# EG701_BMS.net
KiCad netlist of a schematic drawn in Altium Designer
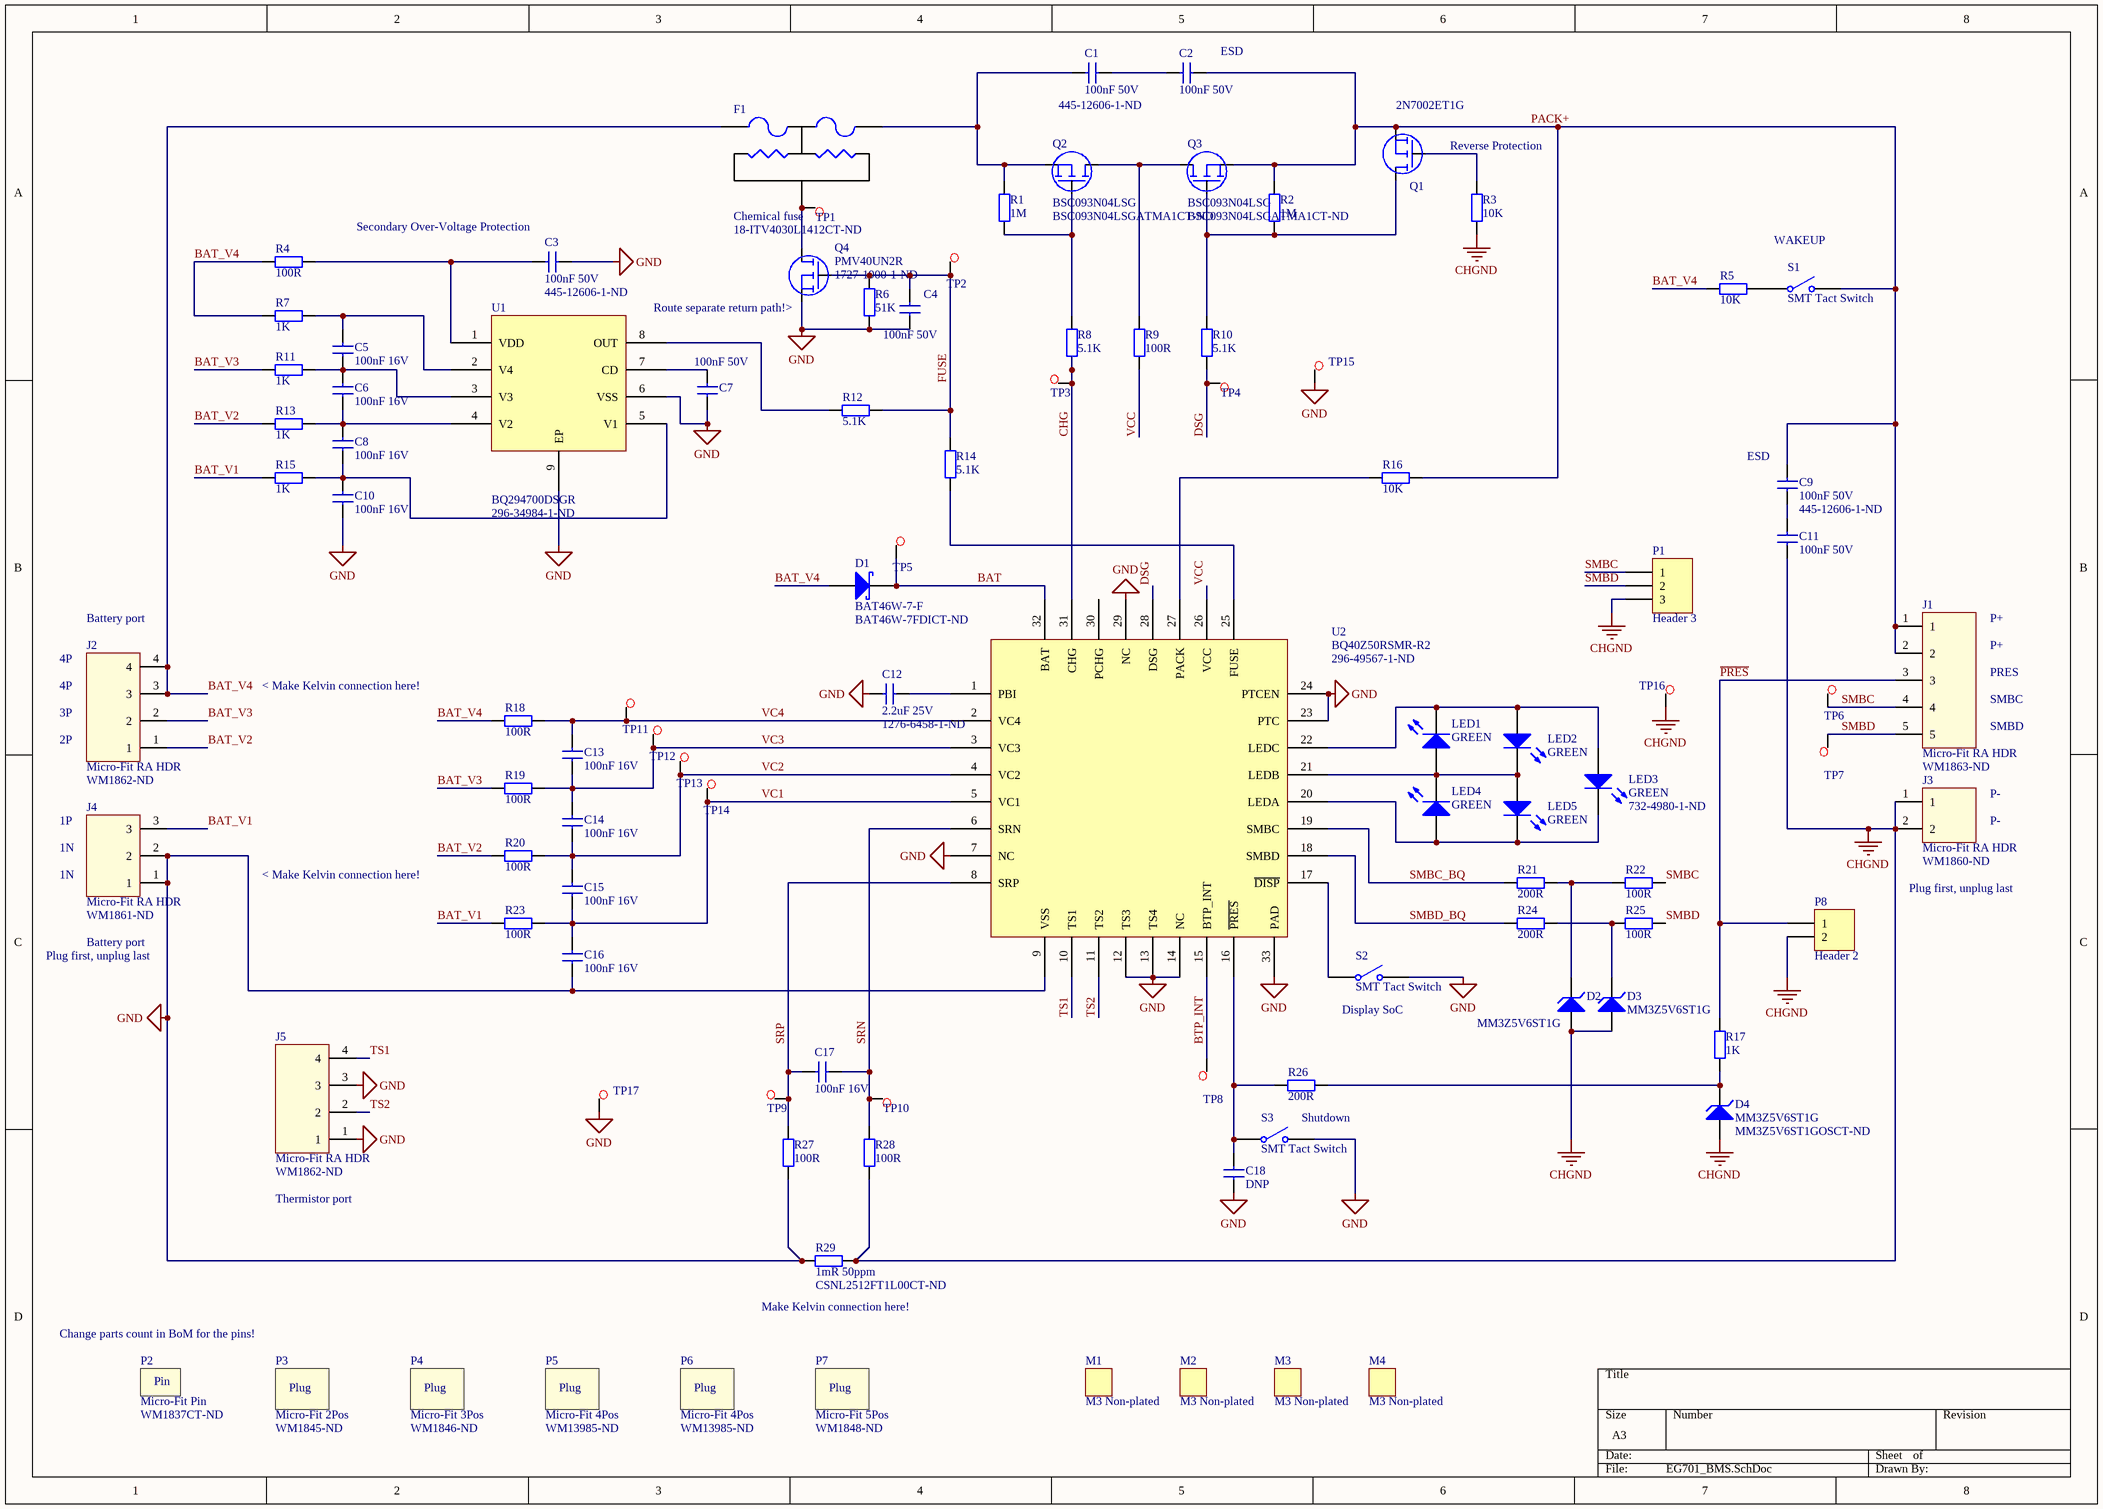
[diagram p0: EG701_BMS.SchDoc]

(export (version "E")
  (design (tool "Eeschema 10.0.6"))
  (components
    (comp (ref "C1")
      (value "100nF 50V")
      (footprint "C0603_GENERIC")
      (fields (field (name "TOLERANCE") "10%") (field (name "SUPPLIER PART NUMBER 1") "445-12606-1-ND"))
      (libsource (lib "FSAE47_Capacitors") (part "100nF_0603_10%_X8R_ 50V"))
    )
    (comp (ref "C2")
      (value "100nF 50V")
      (footprint "C0603_GENERIC")
      (fields (field (name "TOLERANCE") "10%"))
      (libsource (lib "FSAE47_Capacitors") (part "100nF_0603_10%_X8R_ 50V"))
    )
    (comp (ref "C3")
      (value "100nF 50V")
      (footprint "C0603_GENERIC")
      (fields (field (name "TOLERANCE") "10%") (field (name "SUPPLIER PART NUMBER 1") "445-12606-1-ND"))
      (libsource (lib "FSAE47_Capacitors") (part "100nF_0603_10%_X8R_ 50V"))
    )
    (comp (ref "C4")
      (value "100nF 50V")
      (footprint "C0603_GENERIC")
      (fields (field (name "TOLERANCE") "10%"))
      (libsource (lib "FSAE47_Capacitors") (part "100nF_0603_10%_X8R_ 50V"))
    )
    (comp (ref "C5")
      (value "100nF 16V")
      (footprint "C0603_GENERIC")
      (description "Cap Ceramic 0.1uF 16V Y5V -20% to 80% SMD 0603 85C Paper T/R")
      (fields (field (name "TOLERANCE") "80%"))
      (libsource (lib "FSAE47_Capacitors") (part "100nF_0603_-20%+80%_Y5V_16V"))
    )
    (comp (ref "C6")
      (value "100nF 16V")
      (footprint "C0603_GENERIC")
      (description "Cap Ceramic 0.1uF 16V Y5V -20% to 80% SMD 0603 85C Paper T/R")
      (fields (field (name "TOLERANCE") "80%"))
      (libsource (lib "FSAE47_Capacitors") (part "100nF_0603_-20%+80%_Y5V_16V"))
    )
    (comp (ref "C7")
      (value "100nF 50V")
      (footprint "C0603_GENERIC")
      (fields (field (name "TOLERANCE") "10%"))
      (libsource (lib "FSAE47_Capacitors") (part "100nF_0603_10%_X8R_ 50V"))
    )
    (comp (ref "C8")
      (value "100nF 16V")
      (footprint "C0603_GENERIC")
      (description "Cap Ceramic 0.1uF 16V Y5V -20% to 80% SMD 0603 85C Paper T/R")
      (fields (field (name "TOLERANCE") "80%"))
      (libsource (lib "FSAE47_Capacitors") (part "100nF_0603_-20%+80%_Y5V_16V"))
    )
    (comp (ref "C9")
      (value "100nF 50V")
      (footprint "C0603_GENERIC")
      (fields (field (name "TOLERANCE") "10%") (field (name "SUPPLIER PART NUMBER 1") "445-12606-1-ND"))
      (libsource (lib "FSAE47_Capacitors") (part "100nF_0603_10%_X8R_ 50V"))
    )
    (comp (ref "C10")
      (value "100nF 16V")
      (footprint "C0603_GENERIC")
      (description "Cap Ceramic 0.1uF 16V Y5V -20% to 80% SMD 0603 85C Paper T/R")
      (fields (field (name "TOLERANCE") "80%"))
      (libsource (lib "FSAE47_Capacitors") (part "100nF_0603_-20%+80%_Y5V_16V"))
    )
    (comp (ref "C11")
      (value "100nF 50V")
      (footprint "C0603_GENERIC")
      (fields (field (name "TOLERANCE") "10%"))
      (libsource (lib "FSAE47_Capacitors") (part "100nF_0603_10%_X8R_ 50V"))
    )
    (comp (ref "C12")
      (value "2.2uF 25V")
      (footprint "C0603_GENERIC")
      (description "Ceramic capacitor SMD 0805 2.2 µF 25 V 10 %")
      (fields (field (name "TOLERANCE") "10%") (field (name "SUPPLIER PART NUMBER 1") "1276-6458-1-ND"))
      (libsource (lib "EG701_BMS") (part "2U2_0603_10%_X5R_25V"))
    )
    (comp (ref "C13")
      (value "100nF 16V")
      (footprint "C0603_GENERIC")
      (description "Cap Ceramic 0.1uF 16V Y5V -20% to 80% SMD 0603 85C Paper T/R")
      (fields (field (name "TOLERANCE") "80%"))
      (libsource (lib "FSAE47_Capacitors") (part "100nF_0603_-20%+80%_Y5V_16V"))
    )
    (comp (ref "C14")
      (value "100nF 16V")
      (footprint "C0603_GENERIC")
      (description "Cap Ceramic 0.1uF 16V Y5V -20% to 80% SMD 0603 85C Paper T/R")
      (fields (field (name "TOLERANCE") "80%"))
      (libsource (lib "FSAE47_Capacitors") (part "100nF_0603_-20%+80%_Y5V_16V"))
    )
    (comp (ref "C15")
      (value "100nF 16V")
      (footprint "C0603_GENERIC")
      (description "Cap Ceramic 0.1uF 16V Y5V -20% to 80% SMD 0603 85C Paper T/R")
      (fields (field (name "TOLERANCE") "80%"))
      (libsource (lib "FSAE47_Capacitors") (part "100nF_0603_-20%+80%_Y5V_16V"))
    )
    (comp (ref "C16")
      (value "100nF 16V")
      (footprint "C0603_GENERIC")
      (description "Cap Ceramic 0.1uF 16V Y5V -20% to 80% SMD 0603 85C Paper T/R")
      (fields (field (name "TOLERANCE") "80%"))
      (libsource (lib "FSAE47_Capacitors") (part "100nF_0603_-20%+80%_Y5V_16V"))
    )
    (comp (ref "C17")
      (value "100nF 16V")
      (footprint "C0603_GENERIC")
      (description "Cap Ceramic 0.1uF 16V Y5V -20% to 80% SMD 0603 85C Paper T/R")
      (fields (field (name "TOLERANCE") "80%"))
      (libsource (lib "FSAE47_Capacitors") (part "100nF_0603_-20%+80%_Y5V_16V"))
    )
    (comp (ref "C18")
      (value "DNP")
      (footprint "C0603_GENERIC")
      (libsource (lib "FSAE47_Capacitors") (part "SMT_CAP_GENERIC"))
    )
    (comp (ref "D1")
      (value "BAT46W-7-F")
      (footprint "SOD-123_GENERIC")
      (description "Diode Schottky 100V 0.15A 2Pin SOD123")
      (fields (field (name "SUPPLIER PART NUMBER 1") "BAT46W-7FDICT-ND"))
      (libsource (lib "FSAE47_Diodes") (part "BAT46W-7-F"))
    )
    (comp (ref "D2")
      (value "MM3Z5V6ST1G")
      (footprint "SOD_323_GENERIC")
      (description "DIODE ZENER 5.6V 200MW SOD323")
      (fields (field (name "TOLERANCE") "2%"))
      (libsource (lib "EG701_BMS") (part "MM3Z5V6ST1G"))
    )
    (comp (ref "D3")
      (value "MM3Z5V6ST1G")
      (footprint "SOD_323_GENERIC")
      (description "DIODE ZENER 5.6V 200MW SOD323")
      (fields (field (name "TOLERANCE") "2%"))
      (libsource (lib "EG701_BMS") (part "MM3Z5V6ST1G"))
    )
    (comp (ref "D4")
      (value "MM3Z5V6ST1G")
      (footprint "SOD_323_GENERIC")
      (description "DIODE ZENER 5.6V 200MW SOD323")
      (fields (field (name "TOLERANCE") "2%") (field (name "SUPPLIER PART NUMBER 1") "MM3Z5V6ST1GOSCT-ND"))
      (libsource (lib "EG701_BMS") (part "MM3Z5V6ST1G"))
    )
    (comp (ref "F1")
      (value "Chemical fuse")
      (footprint "ITV4030Lxxxx")
      (description "36V 12A controllable fuse")
      (fields (field (name "SUPPLIER PART NUMBER 1") "18-ITV4030L1412CT-ND"))
      (libsource (lib "EG701_BMS") (part "ITV4030L1412"))
    )
    (comp (ref "J1")
      (value "Micro-Fit RA HDR")
      (footprint "436500500")
      (description "CONN HEADER R/A 5POS 3MM")
      (fields (field (name "SUPPLIER PART NUMBER 1") "WM1863-ND"))
      (libsource (lib "EG701_BMS") (part "43650-0500"))
    )
    (comp (ref "J2")
      (value "Micro-Fit RA HDR")
      (footprint "436500400")
      (fields (field (name "SUPPLIER PART NUMBER 1") "WM1862-ND"))
      (libsource (lib "EG701_BMS") (part "43650-0400"))
    )
    (comp (ref "J3")
      (value "Micro-Fit RA HDR")
      (footprint "436500200")
      (description "MOLEX   43650-0200   HEADER, R/A, SINGLE ROW, 2 WAY")
      (fields (field (name "SUPPLIER PART NUMBER 1") "WM1860-ND"))
      (libsource (lib "EG701_BMS") (part "43650-0200"))
    )
    (comp (ref "J4")
      (value "Micro-Fit RA HDR")
      (footprint "436500300")
      (fields (field (name "SUPPLIER PART NUMBER 1") "WM1861-ND"))
      (libsource (lib "EG701_BMS") (part "43650-0300"))
    )
    (comp (ref "J5")
      (value "Micro-Fit RA HDR")
      (footprint "436500400")
      (fields (field (name "SUPPLIER PART NUMBER 1") "WM1862-ND"))
      (libsource (lib "EG701_BMS") (part "43650-0400"))
    )
    (comp (ref "LED1")
      (value "GREEN")
      (footprint "LED_0603_GENERIC")
      (description "WURTH ELEKTRONIK - 150060VS75000 - LED, 0603, B GREEN,  40MCD, 570NM")
      (libsource (lib "FSAE47_Diodes") (part "150060VS75000"))
    )
    (comp (ref "LED2")
      (value "GREEN")
      (footprint "LED_0603_GENERIC")
      (description "WURTH ELEKTRONIK - 150060VS75000 - LED, 0603, B GREEN,  40MCD, 570NM")
      (libsource (lib "FSAE47_Diodes") (part "150060VS75000"))
    )
    (comp (ref "LED3")
      (value "GREEN")
      (footprint "LED_0603_GENERIC")
      (description "WURTH ELEKTRONIK - 150060VS75000 - LED, 0603, B GREEN,  40MCD, 570NM")
      (fields (field (name "SUPPLIER PART NUMBER 1") "732-4980-1-ND"))
      (libsource (lib "FSAE47_Diodes") (part "150060VS75000"))
    )
    (comp (ref "LED4")
      (value "GREEN")
      (footprint "LED_0603_GENERIC")
      (description "WURTH ELEKTRONIK - 150060VS75000 - LED, 0603, B GREEN,  40MCD, 570NM")
      (libsource (lib "FSAE47_Diodes") (part "150060VS75000"))
    )
    (comp (ref "LED5")
      (value "GREEN")
      (footprint "LED_0603_GENERIC")
      (description "WURTH ELEKTRONIK - 150060VS75000 - LED, 0603, B GREEN,  40MCD, 570NM")
      (libsource (lib "FSAE47_Diodes") (part "150060VS75000"))
    )
    (comp (ref "M1")
      (value "M3 Non-plated")
      (footprint "M3_NONPLATED_GENERIC")
      (description "Non-plated mounting hole, M3")
      (libsource (lib "FSAE47_Mechanical") (part "M3_NONPLATED"))
    )
    (comp (ref "M2")
      (value "M3 Non-plated")
      (footprint "M3_NONPLATED_GENERIC")
      (description "Non-plated mounting hole, M3")
      (libsource (lib "FSAE47_Mechanical") (part "M3_NONPLATED"))
    )
    (comp (ref "M3")
      (value "M3 Non-plated")
      (footprint "M3_NONPLATED_GENERIC")
      (description "Non-plated mounting hole, M3")
      (libsource (lib "FSAE47_Mechanical") (part "M3_NONPLATED"))
    )
    (comp (ref "M4")
      (value "M3 Non-plated")
      (footprint "M3_NONPLATED_GENERIC")
      (description "Non-plated mounting hole, M3")
      (libsource (lib "FSAE47_Mechanical") (part "M3_NONPLATED"))
    )
    (comp (ref "P1")
      (value "Header 3")
      (footprint "HDR3_3D")
      (description "Header, 3-Pin")
      (fields (field (name "PUBLISHER") "Altium Limited"))
      (libsource (lib "FSAE47_Connectors") (part "HDR3"))
    )
    (comp (ref "P2")
      (value "Micro-Fit Pin")
      (description "microfit 3.0 female crimp terminal 20-24 awg")
      (fields (field (name "SUPPLIER PART NUMBER 1") "WM1837CT-ND"))
      (libsource (lib "EG701_BMS") (part "43030-0001"))
    )
    (comp (ref "P3")
      (value "Micro-Fit 2Pos")
      (description "Female contact housing single row 3 mm Pole no. 1x2 Micro-Fit, 43645-0200, Molex")
      (fields (field (name "SUPPLIER PART NUMBER 1") "WM1845-ND"))
      (libsource (lib "EG701_BMS") (part "43645-0200"))
    )
    (comp (ref "P4")
      (value "Micro-Fit 3Pos")
      (description "MICRO-FIT 3.0 Series 3mm Pitch 3 Way 1 Row Female Straight PCB Housing 43645")
      (fields (field (name "SUPPLIER PART NUMBER 1") "WM1846-ND"))
      (libsource (lib "EG701_BMS") (part "43645-0300"))
    )
    (comp (ref "P5")
      (value "Micro-Fit 4Pos")
      (description "Conn Housing F 4 POS 3mm Crimp ST Cable Mount Micro-Fit 3.0™ Bag")
      (fields (field (name "SUPPLIER PART NUMBER 1") "WM13985-ND"))
      (libsource (lib "EG701_BMS") (part "43645-0408"))
    )
    (comp (ref "P6")
      (value "Micro-Fit 4Pos")
      (description "Conn Housing F 4 POS 3mm Crimp ST Cable Mount Micro-Fit 3.0™ Bag")
      (fields (field (name "SUPPLIER PART NUMBER 1") "WM13985-ND"))
      (libsource (lib "EG701_BMS") (part "43645-0408"))
    )
    (comp (ref "P7")
      (value "Micro-Fit 5Pos")
      (description "GLOVE, POLYAMIDE, L/FREE, PU, SIZE 6 - More Details")
      (fields (field (name "SUPPLIER PART NUMBER 1") "WM1848-ND"))
      (libsource (lib "EG701_BMS") (part "43645-0500"))
    )
    (comp (ref "P8")
      (value "Header 2")
      (footprint "HDR1X2")
      (description "Header, 2-Pin")
      (fields (field (name "PUBLISHER") "Altium Limited"))
      (libsource (lib "Miscellaneous Connectors") (part "Header 2"))
    )
    (comp (ref "Q1")
      (value "2N7002ET1G")
      (footprint "SOT-23_GENERIC")
      (description "Trans MOSFET N-CH 60V 0.26A 3-Pin SOT-23 T/R")
      (libsource (lib "FSAE47_Transistors") (part "2N7002ET1G"))
    )
    (comp (ref "Q2")
      (value "BSC093N04LSG")
      (footprint "TDSON-8")
      (description "Trans MOSFET N-CH 40V 13A 8-Pin TDSON T/R")
      (fields (field (name "SUPPLIER PART NUMBER 1") "BSC093N04LSGATMA1CT-ND"))
      (libsource (lib "EG701_BMS") (part "BSC093N04LSG"))
    )
    (comp (ref "Q3")
      (value "BSC093N04LSG")
      (footprint "TDSON-8")
      (description "Trans MOSFET N-CH 40V 13A 8-Pin TDSON T/R")
      (fields (field (name "SUPPLIER PART NUMBER 1") "BSC093N04LSGATMA1CT-ND"))
      (libsource (lib "EG701_BMS") (part "BSC093N04LSG"))
    )
    (comp (ref "Q4")
      (value "PMV40UN2R")
      (footprint "SOT-23_GENERIC")
      (description "PMV40UN2 Series 30 V 44 mOhm 3.7 A SMT N-Channel TrenchMOS FET - TO-236AB")
      (fields (field (name "SUPPLIER PART NUMBER 1") "1727-1900-1-ND"))
      (libsource (lib "EG701_BMS") (part "PMV40UN2R"))
    )
    (comp (ref "R1")
      (value "1M")
      (footprint "R0603_GENERIC")
      (description "Yageo RC Series Thick Film Surface Mount Resistor 0603 Case 1M 1% 0.1W 100ppm/C")
      (fields (field (name "TOLERANCE") "1%"))
      (libsource (lib "EG701_BMS") (part "1M_0603_1%_1/10W"))
    )
    (comp (ref "R2")
      (value "1M")
      (footprint "R0603_GENERIC")
      (description "Yageo RC Series Thick Film Surface Mount Resistor 0603 Case 1M 1% 0.1W 100ppm/C")
      (fields (field (name "TOLERANCE") "1%"))
      (libsource (lib "EG701_BMS") (part "1M_0603_1%_1/10W"))
    )
    (comp (ref "R3")
      (value "10K")
      (footprint "R0603_GENERIC")
      (description "RES SMD 10K OHM 1% 1/10W 0603")
      (fields (field (name "TOLERANCE") "1%"))
      (libsource (lib "") (part "10K_0603_1%_1/10W_1"))
    )
    (comp (ref "R4")
      (value "100R")
      (footprint "R0603_GENERIC")
      (description "Res Thick Film 0603 100 Ohm 5% 0.1W(1/10W) ±100ppm/C Molded SMD Paper T/R")
      (fields (field (name "TOLERANCE") "5%"))
      (libsource (lib "EG701_BMS") (part "100R_0603_5%_1/10W"))
    )
    (comp (ref "R5")
      (value "10K")
      (footprint "R0603_GENERIC")
      (description "RES SMD 10K OHM 1% 1/10W 0603")
      (fields (field (name "TOLERANCE") "1%"))
      (libsource (lib "FSAE47_Resistors") (part "10K_0603_1%_1/10W"))
    )
    (comp (ref "R6")
      (value "51K")
      (footprint "R0603_GENERIC")
      (description "RES SMD 51K OHM 1% 1/10W 0603")
      (fields (field (name "TOLERANCE") "1%"))
      (libsource (lib "EG701_BMS") (part "51K_0603_1%_1/10W"))
    )
    (comp (ref "R7")
      (value "1K")
      (footprint "R0603_GENERIC")
      (description "RES SMD 1K OHM 1% 1/10W 0603")
      (fields (field (name "TOLERANCE") "1%"))
      (libsource (lib "FSAE47_Resistors") (part "1K_0603_1%_1/10W"))
    )
    (comp (ref "R8")
      (value "5.1K")
      (footprint "R0603_GENERIC")
      (description "RES SMD 5.1K OHM 1% 1/10W 0603")
      (fields (field (name "TOLERANCE") "1%"))
      (libsource (lib "") (part "5K1_0603_1%_1/10W_1"))
    )
    (comp (ref "R9")
      (value "100R")
      (footprint "R0603_GENERIC")
      (description "Res Thick Film 0603 100 Ohm 5% 0.1W(1/10W) ±100ppm/C Molded SMD Paper T/R")
      (fields (field (name "TOLERANCE") "5%"))
      (libsource (lib "") (part "100R_0603_5%_1/10W_1"))
    )
    (comp (ref "R10")
      (value "5.1K")
      (footprint "R0603_GENERIC")
      (description "RES SMD 5.1K OHM 1% 1/10W 0603")
      (fields (field (name "TOLERANCE") "1%"))
      (libsource (lib "") (part "5K1_0603_1%_1/10W_1"))
    )
    (comp (ref "R11")
      (value "1K")
      (footprint "R0603_GENERIC")
      (description "RES SMD 1K OHM 1% 1/10W 0603")
      (fields (field (name "TOLERANCE") "1%"))
      (libsource (lib "FSAE47_Resistors") (part "1K_0603_1%_1/10W"))
    )
    (comp (ref "R12")
      (value "5.1K")
      (footprint "R0603_GENERIC")
      (description "RES SMD 5.1K OHM 1% 1/10W 0603")
      (fields (field (name "TOLERANCE") "1%"))
      (libsource (lib "EG701_BMS") (part "5K1_0603_1%_1/10W"))
    )
    (comp (ref "R13")
      (value "1K")
      (footprint "R0603_GENERIC")
      (description "RES SMD 1K OHM 1% 1/10W 0603")
      (fields (field (name "TOLERANCE") "1%"))
      (libsource (lib "FSAE47_Resistors") (part "1K_0603_1%_1/10W"))
    )
    (comp (ref "R14")
      (value "5.1K")
      (footprint "R0603_GENERIC")
      (description "RES SMD 5.1K OHM 1% 1/10W 0603")
      (fields (field (name "TOLERANCE") "1%"))
      (libsource (lib "") (part "5K1_0603_1%_1/10W_1"))
    )
    (comp (ref "R15")
      (value "1K")
      (footprint "R0603_GENERIC")
      (description "RES SMD 1K OHM 1% 1/10W 0603")
      (fields (field (name "TOLERANCE") "1%"))
      (libsource (lib "FSAE47_Resistors") (part "1K_0603_1%_1/10W"))
    )
    (comp (ref "R16")
      (value "10K")
      (footprint "R0603_GENERIC")
      (description "RES SMD 10K OHM 1% 1/10W 0603")
      (fields (field (name "TOLERANCE") "1%"))
      (libsource (lib "FSAE47_Resistors") (part "10K_0603_1%_1/10W"))
    )
    (comp (ref "R17")
      (value "1K")
      (footprint "R0603_GENERIC")
      (description "RES SMD 1K OHM 1% 1/10W 0603")
      (fields (field (name "TOLERANCE") "1%"))
      (libsource (lib "") (part "1K_0603_1%_1/10W_1"))
    )
    (comp (ref "R18")
      (value "100R")
      (footprint "R0603_GENERIC")
      (description "Res Thick Film 0603 100 Ohm 5% 0.1W(1/10W) ±100ppm/C Molded SMD Paper T/R")
      (fields (field (name "TOLERANCE") "5%"))
      (libsource (lib "EG701_BMS") (part "100R_0603_5%_1/10W"))
    )
    (comp (ref "R19")
      (value "100R")
      (footprint "R0603_GENERIC")
      (description "Res Thick Film 0603 100 Ohm 5% 0.1W(1/10W) ±100ppm/C Molded SMD Paper T/R")
      (fields (field (name "TOLERANCE") "5%"))
      (libsource (lib "EG701_BMS") (part "100R_0603_5%_1/10W"))
    )
    (comp (ref "R20")
      (value "100R")
      (footprint "R0603_GENERIC")
      (description "Res Thick Film 0603 100 Ohm 5% 0.1W(1/10W) ±100ppm/C Molded SMD Paper T/R")
      (fields (field (name "TOLERANCE") "5%"))
      (libsource (lib "EG701_BMS") (part "100R_0603_5%_1/10W"))
    )
    (comp (ref "R21")
      (value "200R")
      (footprint "R0603_GENERIC")
      (description "RES SMD 200 OHM 1% 1/10W 0603")
      (fields (field (name "TOLERANCE") "1%"))
      (libsource (lib "EG701_BMS") (part "200R_0603_1%_1/10W"))
    )
    (comp (ref "R22")
      (value "100R")
      (footprint "R0603_GENERIC")
      (description "Res Thick Film 0603 100 Ohm 5% 0.1W(1/10W) ±100ppm/C Molded SMD Paper T/R")
      (fields (field (name "TOLERANCE") "5%"))
      (libsource (lib "EG701_BMS") (part "100R_0603_5%_1/10W"))
    )
    (comp (ref "R23")
      (value "100R")
      (footprint "R0603_GENERIC")
      (description "Res Thick Film 0603 100 Ohm 5% 0.1W(1/10W) ±100ppm/C Molded SMD Paper T/R")
      (fields (field (name "TOLERANCE") "5%"))
      (libsource (lib "EG701_BMS") (part "100R_0603_5%_1/10W"))
    )
    (comp (ref "R24")
      (value "200R")
      (footprint "R0603_GENERIC")
      (description "RES SMD 200 OHM 1% 1/10W 0603")
      (fields (field (name "TOLERANCE") "1%"))
      (libsource (lib "EG701_BMS") (part "200R_0603_1%_1/10W"))
    )
    (comp (ref "R25")
      (value "100R")
      (footprint "R0603_GENERIC")
      (description "Res Thick Film 0603 100 Ohm 5% 0.1W(1/10W) ±100ppm/C Molded SMD Paper T/R")
      (fields (field (name "TOLERANCE") "5%"))
      (libsource (lib "EG701_BMS") (part "100R_0603_5%_1/10W"))
    )
    (comp (ref "R26")
      (value "200R")
      (footprint "R0603_GENERIC")
      (description "RES SMD 200 OHM 1% 1/10W 0603")
      (fields (field (name "TOLERANCE") "1%"))
      (libsource (lib "EG701_BMS") (part "200R_0603_1%_1/10W"))
    )
    (comp (ref "R27")
      (value "100R")
      (footprint "R0603_GENERIC")
      (description "Res Thick Film 0603 100 Ohm 5% 0.1W(1/10W) ±100ppm/C Molded SMD Paper T/R")
      (fields (field (name "TOLERANCE") "5%"))
      (libsource (lib "") (part "100R_0603_5%_1/10W_1"))
    )
    (comp (ref "R28")
      (value "100R")
      (footprint "R0603_GENERIC")
      (description "Res Thick Film 0603 100 Ohm 5% 0.1W(1/10W) ±100ppm/C Molded SMD Paper T/R")
      (fields (field (name "TOLERANCE") "5%"))
      (libsource (lib "") (part "100R_0603_5%_1/10W_1"))
    )
    (comp (ref "R29")
      (value "1mR 50ppm")
      (footprint "R2512_M_GENERIC")
      (description "RES 0.001 OHM 1% 2W 2512")
      (fields (field (name "TOLERANCE") "1%") (field (name "SUPPLIER PART NUMBER 1") "CSNL2512FT1L00CT-ND"))
      (libsource (lib "EG701_BMS") (part "0.001R_2512_1%_2W_50ppm"))
    )
    (comp (ref "S1")
      (value "SMT Tact Switch")
      (footprint "41-KRSM6-1")
      (description "SMT tact switch from Hi-Q")
      (libsource (lib "FSAE47_Switches") (part "41-KRSM6-1"))
    )
    (comp (ref "S2")
      (value "SMT Tact Switch")
      (footprint "41-KRSM6-1")
      (description "SMT tact switch from Hi-Q")
      (libsource (lib "FSAE47_Switches") (part "41-KRSM6-1"))
    )
    (comp (ref "S3")
      (value "SMT Tact Switch")
      (footprint "41-KRSM6-1")
      (description "SMT tact switch from Hi-Q")
      (libsource (lib "FSAE47_Switches") (part "41-KRSM6-1"))
    )
    (comp (ref "TP1")
      (value "Test Point TH")
      (footprint "TP_5021")
      (description "Thru Hole Mount Unisulated Test Point")
      (libsource (lib "EG701_BMS") (part "TP_5021"))
    )
    (comp (ref "TP2")
      (value "Test Point TH")
      (footprint "TP_5021")
      (description "Thru Hole Mount Unisulated Test Point")
      (libsource (lib "EG701_BMS") (part "TP_5021"))
    )
    (comp (ref "TP3")
      (value "Test Point TH")
      (footprint "TP_5021")
      (description "Thru Hole Mount Unisulated Test Point")
      (libsource (lib "EG701_BMS") (part "TP_5021"))
    )
    (comp (ref "TP4")
      (value "Test Point TH")
      (footprint "TP_5021")
      (description "Thru Hole Mount Unisulated Test Point")
      (libsource (lib "EG701_BMS") (part "TP_5021"))
    )
    (comp (ref "TP5")
      (value "Test Point TH")
      (footprint "TP_5021")
      (description "Thru Hole Mount Unisulated Test Point")
      (libsource (lib "EG701_BMS") (part "TP_5021"))
    )
    (comp (ref "TP6")
      (value "Test Point TH")
      (footprint "TP_5021")
      (description "Thru Hole Mount Unisulated Test Point")
      (libsource (lib "EG701_BMS") (part "TP_5021"))
    )
    (comp (ref "TP7")
      (value "Test Point TH")
      (footprint "TP_5021")
      (description "Thru Hole Mount Unisulated Test Point")
      (libsource (lib "EG701_BMS") (part "TP_5021"))
    )
    (comp (ref "TP8")
      (value "Test Point TH")
      (footprint "TP_5021")
      (description "Thru Hole Mount Unisulated Test Point")
      (libsource (lib "EG701_BMS") (part "TP_5021"))
    )
    (comp (ref "TP9")
      (value "Test Point TH")
      (footprint "TP_5021")
      (description "Thru Hole Mount Unisulated Test Point")
      (libsource (lib "EG701_BMS") (part "TP_5021"))
    )
    (comp (ref "TP10")
      (value "Test Point TH")
      (footprint "TP_5021")
      (description "Thru Hole Mount Unisulated Test Point")
      (libsource (lib "EG701_BMS") (part "TP_5021"))
    )
    (comp (ref "TP11")
      (value "Test Point TH")
      (footprint "TP_5021")
      (description "Thru Hole Mount Unisulated Test Point")
      (libsource (lib "EG701_BMS") (part "TP_5021"))
    )
    (comp (ref "TP12")
      (value "Test Point TH")
      (footprint "TP_5021")
      (description "Thru Hole Mount Unisulated Test Point")
      (libsource (lib "EG701_BMS") (part "TP_5021"))
    )
    (comp (ref "TP13")
      (value "Test Point TH")
      (footprint "TP_5021")
      (description "Thru Hole Mount Unisulated Test Point")
      (libsource (lib "EG701_BMS") (part "TP_5021"))
    )
    (comp (ref "TP14")
      (value "Test Point TH")
      (footprint "TP_5021")
      (description "Thru Hole Mount Unisulated Test Point")
      (libsource (lib "EG701_BMS") (part "TP_5021"))
    )
    (comp (ref "TP15")
      (value "Test Point TH")
      (footprint "TP_5021")
      (description "Thru Hole Mount Unisulated Test Point")
      (libsource (lib "EG701_BMS") (part "TP_5021"))
    )
    (comp (ref "TP16")
      (value "Test Point TH")
      (footprint "TP_5021")
      (description "Thru Hole Mount Unisulated Test Point")
      (libsource (lib "EG701_BMS") (part "TP_5021"))
    )
    (comp (ref "TP17")
      (value "Test Point TH")
      (footprint "TP_5021")
      (description "Thru Hole Mount Unisulated Test Point")
      (libsource (lib "EG701_BMS") (part "TP_5021"))
    )
    (comp (ref "U1")
      (value "BQ294700DSGR")
      (footprint "SON50P200X80_HS-9N")
      (description "IC BATT PROT 2-4CELL LIION 8WSON")
      (fields (field (name "SUPPLIER PART NUMBER 1") "296-34984-1-ND"))
      (libsource (lib "EG701_BMS") (part "BQ294700DSGR"))
    )
    (comp (ref "U2")
      (value "BQ40Z50RSMR-R2")
      (footprint "QFN40P400X400X100_HS-33N")
      (description "1-4 series Li-ion battery pack manager supporting Turbo Mode 2.0 32-VQFN -40 to 85")
      (fields (field (name "SUPPLIER PART NUMBER 1") "296-49567-1-ND"))
      (libsource (lib "EG701_BMS") (part "BQ40Z50RSMR-R2"))
    )
  )
  (nets
    (net (code "1") (name "/BAT") (class "Default")
      (node (ref "D1") (pin "2") (pinfunction "K_2") (pintype "passive"))
      (node (ref "TP5") (pin "1") (pinfunction "1_1") (pintype "passive"))
      (node (ref "U2") (pin "32") (pinfunction "BAT_32") (pintype "passive"))
    )
    (net (code "2") (name "/BAT_V1") (class "Default")
      (node (ref "J4") (pin "3") (pinfunction "3_3") (pintype "passive"))
      (node (ref "R15") (pin "1") (pinfunction "1_1") (pintype "passive"))
      (node (ref "R23") (pin "1") (pinfunction "1_1") (pintype "passive"))
    )
    (net (code "3") (name "/BAT_V2") (class "Default")
      (node (ref "J2") (pin "1") (pinfunction "1_1") (pintype "passive"))
      (node (ref "R13") (pin "1") (pinfunction "1_1") (pintype "passive"))
      (node (ref "R20") (pin "1") (pinfunction "1_1") (pintype "passive"))
    )
    (net (code "4") (name "/BAT_V3") (class "Default")
      (node (ref "J2") (pin "2") (pinfunction "2_2") (pintype "passive"))
      (node (ref "R11") (pin "1") (pinfunction "1_1") (pintype "passive"))
      (node (ref "R19") (pin "1") (pinfunction "1_1") (pintype "passive"))
    )
    (net (code "5") (name "/BAT_V4") (class "Default")
      (node (ref "D1") (pin "1") (pinfunction "A_1") (pintype "passive"))
      (node (ref "F1") (pin "3") (pinfunction "3_3") (pintype "passive"))
      (node (ref "J2") (pin "3") (pinfunction "3_3") (pintype "passive"))
      (node (ref "J2") (pin "4") (pinfunction "4_4") (pintype "passive"))
      (node (ref "R18") (pin "1") (pinfunction "1_1") (pintype "passive"))
      (node (ref "R4") (pin "1") (pinfunction "1_1") (pintype "passive"))
      (node (ref "R5") (pin "2") (pinfunction "2_2") (pintype "passive"))
      (node (ref "R7") (pin "1") (pinfunction "1_1") (pintype "passive"))
    )
    (net (code "6") (name "/BTP_INT") (class "Default")
      (node (ref "TP8") (pin "1") (pinfunction "1_1") (pintype "passive"))
      (node (ref "U2") (pin "15") (pinfunction "BTP_INT_15") (pintype "passive"))
    )
    (net (code "7") (name "/CHG") (class "Default")
      (node (ref "R8") (pin "1") (pinfunction "1_1") (pintype "passive"))
      (node (ref "TP3") (pin "1") (pinfunction "1_1") (pintype "passive"))
      (node (ref "U2") (pin "31") (pinfunction "CHG_31") (pintype "passive"))
    )
    (net (code "8") (name "/DSG") (class "Default")
      (node (ref "R10") (pin "1") (pinfunction "1_1") (pintype "passive"))
      (node (ref "TP4") (pin "1") (pinfunction "1_1") (pintype "passive"))
      (node (ref "U2") (pin "28") (pinfunction "DSG_28") (pintype "passive"))
    )
    (net (code "9") (name "/FUSE") (class "Default")
      (node (ref "C4") (pin "2") (pinfunction "2_2") (pintype "passive"))
      (node (ref "Q4") (pin "1") (pinfunction "G_1") (pintype "passive"))
      (node (ref "R12") (pin "2") (pinfunction "2_2") (pintype "passive"))
      (node (ref "R14") (pin "2") (pinfunction "2_2") (pintype "passive"))
      (node (ref "R6") (pin "2") (pinfunction "2_2") (pintype "passive"))
      (node (ref "TP2") (pin "1") (pinfunction "1_1") (pintype "passive"))
    )
    (net (code "10") (name "/PACK+") (class "Default")
      (node (ref "C2") (pin "2") (pinfunction "2_2") (pintype "passive"))
      (node (ref "C9") (pin "2") (pinfunction "2_2") (pintype "passive"))
      (node (ref "J1") (pin "1") (pinfunction "1_1") (pintype "passive"))
      (node (ref "J1") (pin "2") (pinfunction "2_2") (pintype "passive"))
      (node (ref "Q1") (pin "1") (pinfunction "S_1") (pintype "passive"))
      (node (ref "Q3") (pin "1") (pinfunction "S_1") (pintype "passive"))
      (node (ref "R16") (pin "1") (pinfunction "1_1") (pintype "passive"))
      (node (ref "R2") (pin "2") (pinfunction "2_2") (pintype "passive"))
      (node (ref "S1") (pin "2") (pinfunction "NO_2") (pintype "passive"))
    )
    (net (code "11") (name "/SMBC") (class "Default")
      (node (ref "J1") (pin "4") (pinfunction "4_4") (pintype "passive"))
      (node (ref "P1") (pin "1") (pinfunction "1_1") (pintype "passive"))
      (node (ref "R22") (pin "2") (pinfunction "2_2") (pintype "passive"))
      (node (ref "TP6") (pin "1") (pinfunction "1_1") (pintype "passive"))
    )
    (net (code "12") (name "/SMBC_BQ") (class "Default")
      (node (ref "R21") (pin "1") (pinfunction "1_1") (pintype "passive"))
      (node (ref "U2") (pin "19") (pinfunction "SMBC_19") (pintype "passive"))
    )
    (net (code "13") (name "/SMBD") (class "Default")
      (node (ref "J1") (pin "5") (pinfunction "5_5") (pintype "passive"))
      (node (ref "P1") (pin "2") (pinfunction "2_2") (pintype "passive"))
      (node (ref "R25") (pin "2") (pinfunction "2_2") (pintype "passive"))
      (node (ref "TP7") (pin "1") (pinfunction "1_1") (pintype "passive"))
    )
    (net (code "14") (name "/SMBD_BQ") (class "Default")
      (node (ref "R24") (pin "1") (pinfunction "1_1") (pintype "passive"))
      (node (ref "U2") (pin "18") (pinfunction "SMBD_18") (pintype "passive"))
    )
    (net (code "15") (name "/SRN") (class "Default")
      (node (ref "C17") (pin "1") (pinfunction "1_1") (pintype "passive"))
      (node (ref "R28") (pin "2") (pinfunction "2_2") (pintype "passive"))
      (node (ref "TP10") (pin "1") (pinfunction "1_1") (pintype "passive"))
      (node (ref "U2") (pin "6") (pinfunction "SRN_6") (pintype "passive"))
    )
    (net (code "16") (name "/SRP") (class "Default")
      (node (ref "C17") (pin "2") (pinfunction "2_2") (pintype "passive"))
      (node (ref "R27") (pin "2") (pinfunction "2_2") (pintype "passive"))
      (node (ref "TP9") (pin "1") (pinfunction "1_1") (pintype "passive"))
      (node (ref "U2") (pin "8") (pinfunction "SRP_8") (pintype "passive"))
    )
    (net (code "17") (name "/TS1") (class "Default")
      (node (ref "J5") (pin "4") (pinfunction "4_4") (pintype "passive"))
      (node (ref "U2") (pin "10") (pinfunction "TS1_10") (pintype "passive"))
    )
    (net (code "18") (name "/TS2") (class "Default")
      (node (ref "J5") (pin "2") (pinfunction "2_2") (pintype "passive"))
      (node (ref "U2") (pin "11") (pinfunction "TS2_11") (pintype "passive"))
    )
    (net (code "19") (name "/VC1") (class "Default")
      (node (ref "C15") (pin "1") (pinfunction "1_1") (pintype "passive"))
      (node (ref "C16") (pin "2") (pinfunction "2_2") (pintype "passive"))
      (node (ref "R23") (pin "2") (pinfunction "2_2") (pintype "passive"))
      (node (ref "TP14") (pin "1") (pinfunction "1_1") (pintype "passive"))
      (node (ref "U2") (pin "5") (pinfunction "VC1_5") (pintype "passive"))
    )
    (net (code "20") (name "/VC2") (class "Default")
      (node (ref "C14") (pin "1") (pinfunction "1_1") (pintype "passive"))
      (node (ref "C15") (pin "2") (pinfunction "2_2") (pintype "passive"))
      (node (ref "R20") (pin "2") (pinfunction "2_2") (pintype "passive"))
      (node (ref "TP13") (pin "1") (pinfunction "1_1") (pintype "passive"))
      (node (ref "U2") (pin "4") (pinfunction "VC2_4") (pintype "passive"))
    )
    (net (code "21") (name "/VC3") (class "Default")
      (node (ref "C13") (pin "1") (pinfunction "1_1") (pintype "passive"))
      (node (ref "C14") (pin "2") (pinfunction "2_2") (pintype "passive"))
      (node (ref "R19") (pin "2") (pinfunction "2_2") (pintype "passive"))
      (node (ref "TP12") (pin "1") (pinfunction "1_1") (pintype "passive"))
      (node (ref "U2") (pin "3") (pinfunction "VC3_3") (pintype "passive"))
    )
    (net (code "22") (name "/VC4") (class "Default")
      (node (ref "C13") (pin "2") (pinfunction "2_2") (pintype "passive"))
      (node (ref "R18") (pin "2") (pinfunction "2_2") (pintype "passive"))
      (node (ref "TP11") (pin "1") (pinfunction "1_1") (pintype "passive"))
      (node (ref "U2") (pin "2") (pinfunction "VC4_2") (pintype "passive"))
    )
    (net (code "23") (name "/VCC") (class "Default")
      (node (ref "R9") (pin "1") (pinfunction "1_1") (pintype "passive"))
      (node (ref "U2") (pin "26") (pinfunction "VCC_26") (pintype "passive"))
    )
    (net (code "24") (name "/~{PRES}") (class "Default")
      (node (ref "J1") (pin "3") (pinfunction "3_3") (pintype "passive"))
      (node (ref "P8") (pin "1") (pinfunction "1_1") (pintype "passive"))
      (node (ref "R17") (pin "2") (pinfunction "2_2") (pintype "passive"))
    )
    (net (code "25") (name "CHGND") (class "Default")
      (node (ref "C11") (pin "1") (pinfunction "1_1") (pintype "passive"))
      (node (ref "D2") (pin "1") (pinfunction "A_1") (pintype "passive"))
      (node (ref "D3") (pin "1") (pinfunction "A_1") (pintype "passive"))
      (node (ref "D4") (pin "1") (pinfunction "A_1") (pintype "passive"))
      (node (ref "J3") (pin "1") (pinfunction "1_1") (pintype "passive"))
      (node (ref "J3") (pin "2") (pinfunction "2_2") (pintype "passive"))
      (node (ref "P1") (pin "3") (pinfunction "3_3") (pintype "passive"))
      (node (ref "P8") (pin "2") (pinfunction "2_2") (pintype "passive"))
      (node (ref "R28") (pin "1") (pinfunction "1_1") (pintype "passive"))
      (node (ref "R29") (pin "2") (pinfunction "2_2") (pintype "passive"))
      (node (ref "R3") (pin "1") (pinfunction "1_1") (pintype "passive"))
      (node (ref "TP16") (pin "1") (pinfunction "1_1") (pintype "passive"))
    )
    (net (code "26") (name "GND") (class "Default")
      (node (ref "C10") (pin "1") (pinfunction "1_1") (pintype "passive"))
      (node (ref "C12") (pin "2") (pinfunction "2_2") (pintype "passive"))
      (node (ref "C16") (pin "1") (pinfunction "1_1") (pintype "passive"))
      (node (ref "C18") (pin "1") (pinfunction "1_1") (pintype "passive"))
      (node (ref "C3") (pin "1") (pinfunction "1_1") (pintype "passive"))
      (node (ref "C4") (pin "1") (pinfunction "1_1") (pintype "passive"))
      (node (ref "C7") (pin "1") (pinfunction "1_1") (pintype "passive"))
      (node (ref "J4") (pin "1") (pinfunction "1_1") (pintype "passive"))
      (node (ref "J4") (pin "2") (pinfunction "2_2") (pintype "passive"))
      (node (ref "J5") (pin "1") (pinfunction "1_1") (pintype "passive"))
      (node (ref "J5") (pin "3") (pinfunction "3_3") (pintype "passive"))
      (node (ref "Q4") (pin "2") (pinfunction "S_2") (pintype "passive"))
      (node (ref "R27") (pin "1") (pinfunction "1_1") (pintype "passive"))
      (node (ref "R29") (pin "1") (pinfunction "1_1") (pintype "passive"))
      (node (ref "R6") (pin "1") (pinfunction "1_1") (pintype "passive"))
      (node (ref "S2") (pin "2") (pinfunction "NO_2") (pintype "passive"))
      (node (ref "S3") (pin "2") (pinfunction "NO_2") (pintype "passive"))
      (node (ref "TP15") (pin "1") (pinfunction "1_1") (pintype "passive"))
      (node (ref "TP17") (pin "1") (pinfunction "1_1") (pintype "passive"))
      (node (ref "U1") (pin "6") (pinfunction "VSS_6") (pintype "passive"))
      (node (ref "U1") (pin "9") (pinfunction "EP_9") (pintype "passive"))
      (node (ref "U2") (pin "12") (pinfunction "TS3_12") (pintype "passive"))
      (node (ref "U2") (pin "13") (pinfunction "TS4_13") (pintype "passive"))
      (node (ref "U2") (pin "14") (pinfunction "NC_14") (pintype "passive"))
      (node (ref "U2") (pin "23") (pinfunction "PTC_23") (pintype "passive"))
      (node (ref "U2") (pin "24") (pinfunction "PTCEN_24") (pintype "passive"))
      (node (ref "U2") (pin "29") (pinfunction "NC_29") (pintype "passive"))
      (node (ref "U2") (pin "33") (pinfunction "PAD_33") (pintype "passive"))
      (node (ref "U2") (pin "7") (pinfunction "NC_7") (pintype "passive"))
      (node (ref "U2") (pin "9") (pinfunction "VSS_9") (pintype "passive"))
    )
    (net (code "27") (name "Net-(C1-Pad2)") (class "Default")
      (node (ref "C1") (pin "2") (pinfunction "2_2") (pintype "passive"))
      (node (ref "C2") (pin "1") (pinfunction "1_1") (pintype "passive"))
    )
    (net (code "28") (name "Net-(C11-Pad2)") (class "Default")
      (node (ref "C11") (pin "2") (pinfunction "2_2") (pintype "passive"))
      (node (ref "C9") (pin "1") (pinfunction "1_1") (pintype "passive"))
    )
    (net (code "29") (name "Net-(D2-K)") (class "Default")
      (node (ref "D2") (pin "2") (pinfunction "K_2") (pintype "passive"))
      (node (ref "R21") (pin "2") (pinfunction "2_2") (pintype "passive"))
      (node (ref "R22") (pin "1") (pinfunction "1_1") (pintype "passive"))
    )
    (net (code "30") (name "Net-(D3-K)") (class "Default")
      (node (ref "D3") (pin "2") (pinfunction "K_2") (pintype "passive"))
      (node (ref "R24") (pin "2") (pinfunction "2_2") (pintype "passive"))
      (node (ref "R25") (pin "1") (pinfunction "1_1") (pintype "passive"))
    )
    (net (code "31") (name "Net-(D4-K)") (class "Default")
      (node (ref "D4") (pin "2") (pinfunction "K_2") (pintype "passive"))
      (node (ref "R17") (pin "1") (pinfunction "1_1") (pintype "passive"))
      (node (ref "R26") (pin "2") (pinfunction "2_2") (pintype "passive"))
    )
    (net (code "32") (name "Net-(LED1-A)") (class "Default")
      (node (ref "LED1") (pin "2") (pinfunction "A_2") (pintype "passive"))
      (node (ref "LED2") (pin "1") (pinfunction "K_1") (pintype "passive"))
      (node (ref "LED4") (pin "1") (pinfunction "K_1") (pintype "passive"))
      (node (ref "LED5") (pin "2") (pinfunction "A_2") (pintype "passive"))
      (node (ref "U2") (pin "21") (pinfunction "LEDB_21") (pintype "passive"))
    )
    (net (code "33") (name "Net-(LED1-K)") (class "Default")
      (node (ref "LED1") (pin "1") (pinfunction "K_1") (pintype "passive"))
      (node (ref "LED2") (pin "2") (pinfunction "A_2") (pintype "passive"))
      (node (ref "LED3") (pin "2") (pinfunction "A_2") (pintype "passive"))
      (node (ref "U2") (pin "22") (pinfunction "LEDC_22") (pintype "passive"))
    )
    (net (code "34") (name "Net-(LED3-K)") (class "Default")
      (node (ref "LED3") (pin "1") (pinfunction "K_1") (pintype "passive"))
      (node (ref "LED4") (pin "2") (pinfunction "A_2") (pintype "passive"))
      (node (ref "LED5") (pin "1") (pinfunction "K_1") (pintype "passive"))
      (node (ref "U2") (pin "20") (pinfunction "LEDA_20") (pintype "passive"))
    )
    (net (code "35") (name "Net-(Q1-D)") (class "Default")
      (node (ref "Q1") (pin "3") (pinfunction "D_3") (pintype "passive"))
      (node (ref "Q3") (pin "4") (pinfunction "G_4") (pintype "passive"))
      (node (ref "R10") (pin "2") (pinfunction "2_2") (pintype "passive"))
      (node (ref "R2") (pin "1") (pinfunction "1_1") (pintype "passive"))
    )
    (net (code "36") (name "Net-(Q1-G)") (class "Default")
      (node (ref "Q1") (pin "2") (pinfunction "G_2") (pintype "passive"))
      (node (ref "R3") (pin "2") (pinfunction "2_2") (pintype "passive"))
    )
    (net (code "37") (name "Net-(Q2-D)") (class "Default")
      (node (ref "Q2") (pin "5") (pinfunction "D_5") (pintype "passive"))
      (node (ref "Q3") (pin "5") (pinfunction "D_5") (pintype "passive"))
      (node (ref "R9") (pin "2") (pinfunction "2_2") (pintype "passive"))
    )
    (net (code "38") (name "Net-(Q2-G)") (class "Default")
      (node (ref "Q2") (pin "4") (pinfunction "G_4") (pintype "passive"))
      (node (ref "R1") (pin "1") (pinfunction "1_1") (pintype "passive"))
      (node (ref "R8") (pin "2") (pinfunction "2_2") (pintype "passive"))
    )
    (net (code "39") (name "Net-(Q2-S)") (class "Default")
      (node (ref "C1") (pin "1") (pinfunction "1_1") (pintype "passive"))
      (node (ref "F1") (pin "1") (pinfunction "1_1") (pintype "passive"))
      (node (ref "Q2") (pin "1") (pinfunction "S_1") (pintype "passive"))
      (node (ref "R1") (pin "2") (pinfunction "2_2") (pintype "passive"))
    )
    (net (code "40") (name "Net-(Q4-D)") (class "Default")
      (node (ref "F1") (pin "2") (pinfunction "2_2") (pintype "passive"))
      (node (ref "Q4") (pin "3") (pinfunction "D_3") (pintype "passive"))
      (node (ref "TP1") (pin "1") (pinfunction "1_1") (pintype "passive"))
    )
    (net (code "41") (name "Net-(S1-COMMON)") (class "Default")
      (node (ref "R5") (pin "1") (pinfunction "1_1") (pintype "passive"))
      (node (ref "S1") (pin "1") (pinfunction "COMMON_1") (pintype "passive"))
    )
    (net (code "42") (name "Net-(S2-COMMON)") (class "Default")
      (node (ref "S2") (pin "1") (pinfunction "COMMON_1") (pintype "passive"))
      (node (ref "U2") (pin "17") (pinfunction "~{DISP}_17") (pintype "passive"))
    )
    (net (code "43") (name "Net-(S3-COMMON)") (class "Default")
      (node (ref "C18") (pin "2") (pinfunction "2_2") (pintype "passive"))
      (node (ref "R26") (pin "1") (pinfunction "1_1") (pintype "passive"))
      (node (ref "S3") (pin "1") (pinfunction "COMMON_1") (pintype "passive"))
      (node (ref "U2") (pin "16") (pinfunction "~{PRES}_16") (pintype "passive"))
    )
    (net (code "44") (name "Net-(U1-CD)") (class "Default")
      (node (ref "C7") (pin "2") (pinfunction "2_2") (pintype "passive"))
      (node (ref "U1") (pin "7") (pinfunction "CD_7") (pintype "passive"))
    )
    (net (code "45") (name "Net-(U1-OUT)") (class "Default")
      (node (ref "R12") (pin "1") (pinfunction "1_1") (pintype "passive"))
      (node (ref "U1") (pin "8") (pinfunction "OUT_8") (pintype "passive"))
    )
    (net (code "46") (name "Net-(U1-V1)") (class "Default")
      (node (ref "C10") (pin "2") (pinfunction "2_2") (pintype "passive"))
      (node (ref "C8") (pin "1") (pinfunction "1_1") (pintype "passive"))
      (node (ref "R15") (pin "2") (pinfunction "2_2") (pintype "passive"))
      (node (ref "U1") (pin "5") (pinfunction "V1_5") (pintype "passive"))
    )
    (net (code "47") (name "Net-(U1-V2)") (class "Default")
      (node (ref "C6") (pin "1") (pinfunction "1_1") (pintype "passive"))
      (node (ref "C8") (pin "2") (pinfunction "2_2") (pintype "passive"))
      (node (ref "R13") (pin "2") (pinfunction "2_2") (pintype "passive"))
      (node (ref "U1") (pin "4") (pinfunction "V2_4") (pintype "passive"))
    )
    (net (code "48") (name "Net-(U1-V3)") (class "Default")
      (node (ref "C5") (pin "1") (pinfunction "1_1") (pintype "passive"))
      (node (ref "C6") (pin "2") (pinfunction "2_2") (pintype "passive"))
      (node (ref "R11") (pin "2") (pinfunction "2_2") (pintype "passive"))
      (node (ref "U1") (pin "3") (pinfunction "V3_3") (pintype "passive"))
    )
    (net (code "49") (name "Net-(U1-V4)") (class "Default")
      (node (ref "C5") (pin "2") (pinfunction "2_2") (pintype "passive"))
      (node (ref "R7") (pin "2") (pinfunction "2_2") (pintype "passive"))
      (node (ref "U1") (pin "2") (pinfunction "V4_2") (pintype "passive"))
    )
    (net (code "50") (name "Net-(U1-VDD)") (class "Default")
      (node (ref "C3") (pin "2") (pinfunction "2_2") (pintype "passive"))
      (node (ref "R4") (pin "2") (pinfunction "2_2") (pintype "passive"))
      (node (ref "U1") (pin "1") (pinfunction "VDD_1") (pintype "passive"))
    )
    (net (code "51") (name "Net-(U2-FUSE)") (class "Default")
      (node (ref "R14") (pin "1") (pinfunction "1_1") (pintype "passive"))
      (node (ref "U2") (pin "25") (pinfunction "FUSE_25") (pintype "passive"))
    )
    (net (code "52") (name "Net-(U2-PACK)") (class "Default")
      (node (ref "R16") (pin "2") (pinfunction "2_2") (pintype "passive"))
      (node (ref "U2") (pin "27") (pinfunction "PACK_27") (pintype "passive"))
    )
    (net (code "53") (name "Net-(U2-PBI)") (class "Default")
      (node (ref "C12") (pin "1") (pinfunction "1_1") (pintype "passive"))
      (node (ref "U2") (pin "1") (pinfunction "PBI_1") (pintype "passive"))
    )
    (net (code "54") (name "unconnected-(U2-PCHG-Pad30)") (class "Default")
      (node (ref "U2") (pin "30") (pinfunction "PCHG_30") (pintype "passive"))
    )
  )
)
